# Sheet1.net
KiCad netlist of a schematic drawn in Altium Designer
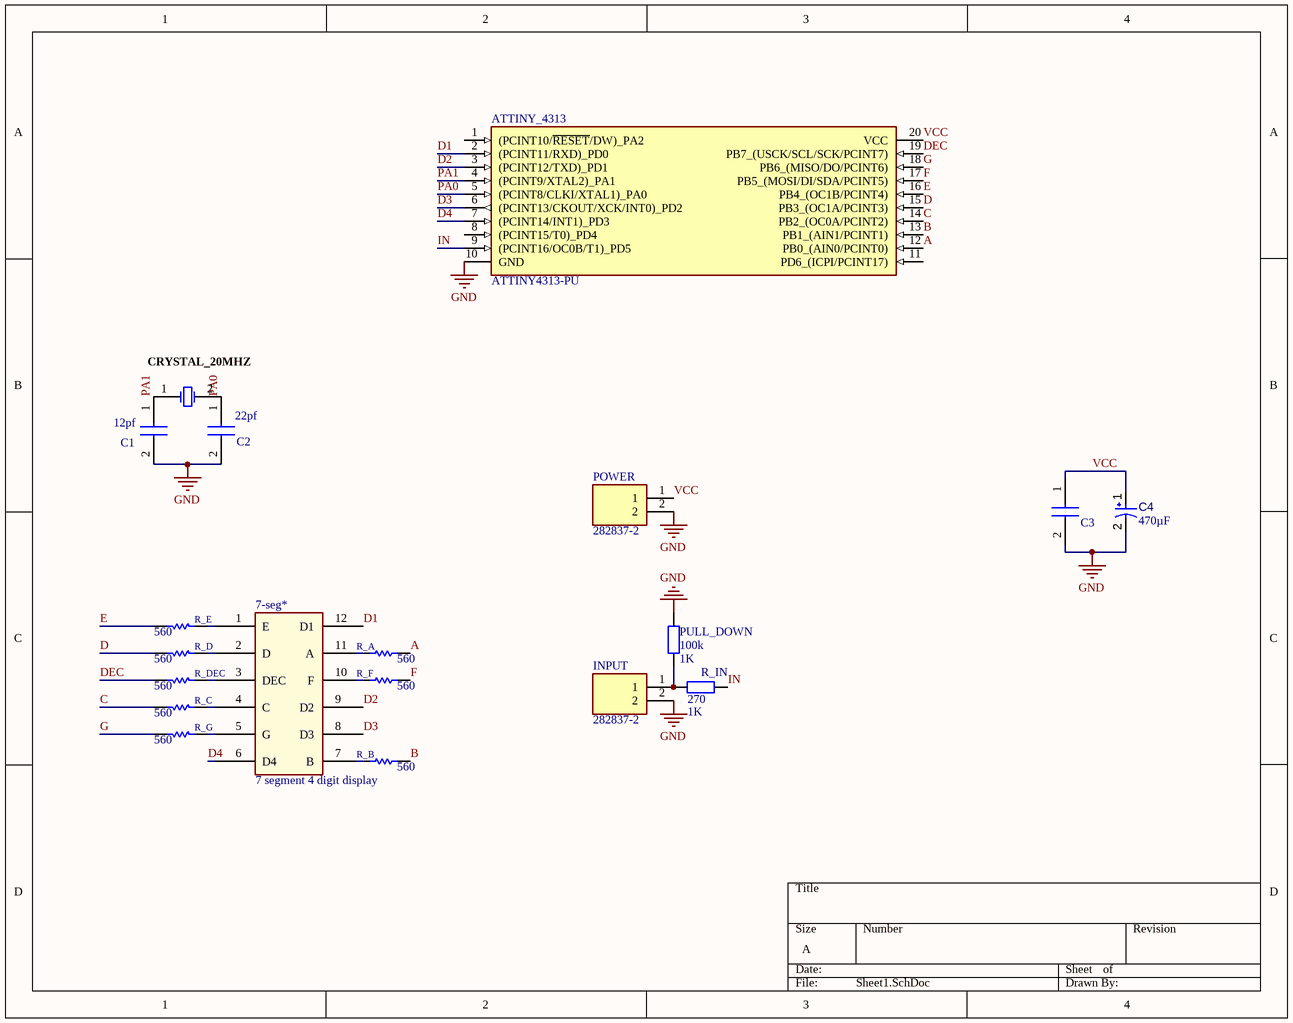
[diagram p0: Sheet1.SchDoc]

(export (version "E")
  (design (tool "Eeschema 10.0.6"))
  (components
    (comp (ref "7-seg*")
      (value "7 segment 4 digit display")
      (footprint "PCBComponent_1")
      (libsource (lib "7seg") (part "7 segment 4 digit display"))
    )
    (comp (ref "ATTINY_4313")
      (value "ATTINY4313-PU")
      (footprint "SamacSys:DIP794W56P254L2574H533Q20N")
      (description "Integrated Circuit")
      (fields (field (name "MOUSER PART NUMBER") "556-ATTINY4313-PU"))
      (libsource (lib "*") (part "ATTINY4313-PU"))
    )
    (comp (ref "C1")
      (value "12pf")
      (footprint "SamacSys:C320C104KCR5TA")
      (description "Capacitor")
      (fields
        (field (name "MANUFACTURER_PART_NUMBER") "C320C104KCR5TA")
        (field (name "MOUSER PART NUMBER") "80-C320C104KCR")
      )
      (libsource (lib "*") (part "C320C104KCR5TA"))
    )
    (comp (ref "C2")
      (value "22pf")
      (footprint "SamacSys:C320C104KCR5TA")
      (description "Capacitor")
      (fields
        (field (name "MANUFACTURER_PART_NUMBER") "C320C104KCR5TA")
        (field (name "MOUSER PART NUMBER") "80-C320C104KCR")
      )
      (libsource (lib "*") (part "C320C104KCR5TA"))
    )
    (comp (ref "C3")
      (value "C320C104KCR5TA")
      (footprint "SamacSys:C320C104KCR5TA")
      (description "Capacitor")
      (fields (field (name "MOUSER PART NUMBER") "80-C320C104KCR"))
      (libsource (lib "*") (part "C320C104KCR5TA"))
    )
    (comp (ref "C4")
      (value "470µF")
      (footprint "CAPPR65-350-1150X800X1250")
      (description "Aluminum Electrolytic Capacitor, 100 uF, +/- 20%, 50 V, -40 to 85 degC, 2-Pin THD, RoHS, Bulk")
      (fields (field (name "MANUFACTURER") "Panasonic") (field (name "TOLERANCE") "20%"))
      (libsource (lib "Ground Robotics") (part "CAP-P-2"))
    )
    (comp (ref "CRYSTAL_20MHZ")
      (value "FOXSLF/080-20")
      (footprint "FOX-FOXSLF080-20")
      (description "Resistance Weld Thru-Hole Crystal, 8 MHz, +/- 50 ppm, 10 pF, -20 to 70 degC, 2-Pin THD, RoHS, Bulk")
      (fields (field (name "MANUFACTURER") "FOX Electronics") (field (name "TOLERANCE") "50ppm"))
      (libsource (lib "Ground Robotics") (part "XTAL-1-2-2"))
    )
    (comp (ref "INPUT")
      (value "282837-2")
      (footprint "SamacSys:2828372")
      (description "Connector")
      (fields (field (name "MOUSER PART NUMBER") "571-2828372"))
      (libsource (lib "*") (part "282837-2"))
    )
    (comp (ref "POWER")
      (value "282837-2")
      (footprint "SamacSys:2828372")
      (description "Connector")
      (fields (field (name "MOUSER PART NUMBER") "571-2828372"))
      (libsource (lib "*") (part "282837-2"))
    )
    (comp (ref "PULL_DOWN")
      (value "100k")
      (footprint "AXIAL-0.4")
      (description "Resistor")
      (fields (field (name "ALTIUM_VALUE") "1K") (field (name "PUBLISHER") "Altium Limited"))
      (libsource (lib "Miscellaneous Devices") (part "Res2"))
    )
    (comp (ref "R_A")
      (value "560")
      (footprint "AXIAL-0.3")
      (description "Resistor")
      (fields (field (name "Comment") "Res1") (field (name "PUBLISHER") "Altium Limited"))
      (libsource (lib "Miscellaneous Devices") (part "Res1"))
    )
    (comp (ref "R_B")
      (value "560")
      (footprint "AXIAL-0.3")
      (description "Resistor")
      (fields (field (name "Comment") "Res1") (field (name "PUBLISHER") "Altium Limited"))
      (libsource (lib "Miscellaneous Devices") (part "Res1"))
    )
    (comp (ref "R_C")
      (value "560")
      (footprint "AXIAL-0.3")
      (description "Resistor")
      (fields (field (name "Comment") "Res1") (field (name "PUBLISHER") "Altium Limited"))
      (libsource (lib "Miscellaneous Devices") (part "Res1"))
    )
    (comp (ref "R_D")
      (value "560")
      (footprint "AXIAL-0.3")
      (description "Resistor")
      (fields (field (name "Comment") "Res1") (field (name "PUBLISHER") "Altium Limited"))
      (libsource (lib "Miscellaneous Devices") (part "Res1"))
    )
    (comp (ref "R_DEC")
      (value "560")
      (footprint "AXIAL-0.3")
      (description "Resistor")
      (fields (field (name "Comment") "Res1") (field (name "PUBLISHER") "Altium Limited"))
      (libsource (lib "Miscellaneous Devices") (part "Res1"))
    )
    (comp (ref "R_E")
      (value "560")
      (footprint "AXIAL-0.3")
      (description "Resistor")
      (fields (field (name "Comment") "Res1") (field (name "PUBLISHER") "Altium Limited"))
      (libsource (lib "Miscellaneous Devices") (part "Res1"))
    )
    (comp (ref "R_F")
      (value "560")
      (footprint "AXIAL-0.3")
      (description "Resistor")
      (fields (field (name "Comment") "Res1") (field (name "PUBLISHER") "Altium Limited"))
      (libsource (lib "Miscellaneous Devices") (part "Res1"))
    )
    (comp (ref "R_G")
      (value "560")
      (footprint "AXIAL-0.3")
      (description "Resistor")
      (fields (field (name "Comment") "Res1") (field (name "PUBLISHER") "Altium Limited"))
      (libsource (lib "Miscellaneous Devices") (part "Res1"))
    )
    (comp (ref "R_IN")
      (value "270")
      (footprint "AXIAL-0.4")
      (description "Resistor")
      (fields (field (name "ALTIUM_VALUE") "1K") (field (name "PUBLISHER") "Altium Limited"))
      (libsource (lib "") (part "Res2_1"))
    )
  )
  (nets
    (net (code "1") (name "/A") (class "Default")
      (node (ref "ATTINY_4313") (pin "12") (pinfunction "PB0_(AIN0/PCINT0)_12") (pintype "input"))
      (node (ref "R_A") (pin "2") (pinfunction "2_2") (pintype "passive"))
    )
    (net (code "2") (name "/B") (class "Default")
      (node (ref "ATTINY_4313") (pin "13") (pinfunction "PB1_(AIN1/PCINT1)_13") (pintype "input"))
      (node (ref "R_B") (pin "2") (pinfunction "2_2") (pintype "passive"))
    )
    (net (code "3") (name "/C") (class "Default")
      (node (ref "ATTINY_4313") (pin "14") (pinfunction "PB2_(OC0A/PCINT2)_14") (pintype "input"))
      (node (ref "R_C") (pin "2") (pinfunction "2_2") (pintype "passive"))
    )
    (net (code "4") (name "/D") (class "Default")
      (node (ref "ATTINY_4313") (pin "15") (pinfunction "PB3_(OC1A/PCINT3)_15") (pintype "input"))
      (node (ref "R_D") (pin "2") (pinfunction "2_2") (pintype "passive"))
    )
    (net (code "5") (name "/D1") (class "Default")
      (node (ref "7-seg*") (pin "12") (pinfunction "D1_12") (pintype "passive"))
      (node (ref "ATTINY_4313") (pin "2") (pinfunction "(PCINT11/RXD)_PD0_2") (pintype "input"))
    )
    (net (code "6") (name "/D2") (class "Default")
      (node (ref "7-seg*") (pin "9") (pinfunction "D2_9") (pintype "passive"))
      (node (ref "ATTINY_4313") (pin "3") (pinfunction "(PCINT12/TXD)_PD1_3") (pintype "input"))
    )
    (net (code "7") (name "/D3") (class "Default")
      (node (ref "7-seg*") (pin "8") (pinfunction "D3_8") (pintype "passive"))
      (node (ref "ATTINY_4313") (pin "6") (pinfunction "(PCINT13/CKOUT/XCK/INT0)_PD2_6") (pintype "output"))
    )
    (net (code "8") (name "/D4") (class "Default")
      (node (ref "7-seg*") (pin "6") (pinfunction "D4_6") (pintype "passive"))
      (node (ref "ATTINY_4313") (pin "7") (pinfunction "(PCINT14/INT1)_PD3_7") (pintype "input"))
    )
    (net (code "9") (name "/DEC") (class "Default")
      (node (ref "ATTINY_4313") (pin "19") (pinfunction "PB7_(USCK/SCL/SCK/PCINT7)_19") (pintype "input"))
      (node (ref "R_DEC") (pin "2") (pinfunction "2_2") (pintype "passive"))
    )
    (net (code "10") (name "/E") (class "Default")
      (node (ref "ATTINY_4313") (pin "16") (pinfunction "PB4_(OC1B/PCINT4)_16") (pintype "input"))
      (node (ref "R_E") (pin "2") (pinfunction "2_2") (pintype "passive"))
    )
    (net (code "11") (name "/F") (class "Default")
      (node (ref "ATTINY_4313") (pin "17") (pinfunction "PB5_(MOSI/DI/SDA/PCINT5)_17") (pintype "input"))
      (node (ref "R_F") (pin "2") (pinfunction "2_2") (pintype "passive"))
    )
    (net (code "12") (name "/G") (class "Default")
      (node (ref "ATTINY_4313") (pin "18") (pinfunction "PB6_(MISO/DO/PCINT6)_18") (pintype "input"))
      (node (ref "R_G") (pin "2") (pinfunction "2_2") (pintype "passive"))
    )
    (net (code "13") (name "/IN") (class "Default")
      (node (ref "ATTINY_4313") (pin "9") (pinfunction "(PCINT16/OC0B/T1)_PD5_9") (pintype "input"))
      (node (ref "R_IN") (pin "1") (pinfunction "1_1") (pintype "passive"))
    )
    (net (code "14") (name "/PA0") (class "Default")
      (node (ref "ATTINY_4313") (pin "5") (pinfunction "(PCINT8/CLKI/XTAL1)_PA0_5") (pintype "input"))
      (node (ref "C2") (pin "1") (pinfunction "1_1") (pintype "passive"))
      (node (ref "CRYSTAL_20MHZ") (pin "2") (pinfunction "2_2") (pintype "passive"))
    )
    (net (code "15") (name "/PA1") (class "Default")
      (node (ref "ATTINY_4313") (pin "4") (pinfunction "(PCINT9/XTAL2)_PA1_4") (pintype "input"))
      (node (ref "C1") (pin "1") (pinfunction "1_1") (pintype "passive"))
      (node (ref "CRYSTAL_20MHZ") (pin "1") (pinfunction "1_1") (pintype "passive"))
    )
    (net (code "16") (name "/VCC") (class "Default")
      (node (ref "ATTINY_4313") (pin "20") (pinfunction "VCC_20") (pintype "power_in"))
      (node (ref "C3") (pin "1") (pinfunction "1_1") (pintype "passive"))
      (node (ref "C4") (pin "1") (pinfunction "1_1") (pintype "passive"))
      (node (ref "POWER") (pin "1") (pinfunction "1_1") (pintype "passive"))
    )
    (net (code "17") (name "GND") (class "Default")
      (node (ref "ATTINY_4313") (pin "10") (pinfunction "GND_10") (pintype "power_in"))
      (node (ref "C1") (pin "2") (pinfunction "2_2") (pintype "passive"))
      (node (ref "C2") (pin "2") (pinfunction "2_2") (pintype "passive"))
      (node (ref "C3") (pin "2") (pinfunction "2_2") (pintype "passive"))
      (node (ref "C4") (pin "2") (pinfunction "2_2") (pintype "passive"))
      (node (ref "INPUT") (pin "2") (pinfunction "2_2") (pintype "passive"))
      (node (ref "POWER") (pin "2") (pinfunction "2_2") (pintype "passive"))
      (node (ref "PULL_DOWN") (pin "2") (pinfunction "2_2") (pintype "passive"))
    )
    (net (code "18") (name "Net-(7-seg*-A)") (class "Default")
      (node (ref "7-seg*") (pin "11") (pinfunction "A_11") (pintype "passive"))
      (node (ref "R_A") (pin "1") (pinfunction "1_1") (pintype "passive"))
    )
    (net (code "19") (name "Net-(7-seg*-B)") (class "Default")
      (node (ref "7-seg*") (pin "7") (pinfunction "B_7") (pintype "passive"))
      (node (ref "R_B") (pin "1") (pinfunction "1_1") (pintype "passive"))
    )
    (net (code "20") (name "Net-(7-seg*-C)") (class "Default")
      (node (ref "7-seg*") (pin "4") (pinfunction "C_4") (pintype "passive"))
      (node (ref "R_C") (pin "1") (pinfunction "1_1") (pintype "passive"))
    )
    (net (code "21") (name "Net-(7-seg*-D)") (class "Default")
      (node (ref "7-seg*") (pin "2") (pinfunction "D_2") (pintype "passive"))
      (node (ref "R_D") (pin "1") (pinfunction "1_1") (pintype "passive"))
    )
    (net (code "22") (name "Net-(7-seg*-DEC)") (class "Default")
      (node (ref "7-seg*") (pin "3") (pinfunction "DEC_3") (pintype "passive"))
      (node (ref "R_DEC") (pin "1") (pinfunction "1_1") (pintype "passive"))
    )
    (net (code "23") (name "Net-(7-seg*-E)") (class "Default")
      (node (ref "7-seg*") (pin "1") (pinfunction "E_1") (pintype "passive"))
      (node (ref "R_E") (pin "1") (pinfunction "1_1") (pintype "passive"))
    )
    (net (code "24") (name "Net-(7-seg*-F)") (class "Default")
      (node (ref "7-seg*") (pin "10") (pinfunction "F_10") (pintype "passive"))
      (node (ref "R_F") (pin "1") (pinfunction "1_1") (pintype "passive"))
    )
    (net (code "25") (name "Net-(7-seg*-G)") (class "Default")
      (node (ref "7-seg*") (pin "5") (pinfunction "G_5") (pintype "passive"))
      (node (ref "R_G") (pin "1") (pinfunction "1_1") (pintype "passive"))
    )
    (net (code "26") (name "Net-(INPUT-Pad1)") (class "Default")
      (node (ref "INPUT") (pin "1") (pinfunction "1_1") (pintype "passive"))
      (node (ref "PULL_DOWN") (pin "1") (pinfunction "1_1") (pintype "passive"))
      (node (ref "R_IN") (pin "2") (pinfunction "2_2") (pintype "passive"))
    )
    (net (code "27") (name "unconnected-(ATTINY_4313-(PCINT10{slash}~{RESET}{slash}DW)_PA2-Pad1)") (class "Default")
      (node (ref "ATTINY_4313") (pin "1") (pinfunction "(PCINT10/~{RESET}/DW)_PA2_1") (pintype "input"))
    )
    (net (code "28") (name "unconnected-(ATTINY_4313-(PCINT15{slash}T0)_PD4-Pad8)") (class "Default")
      (node (ref "ATTINY_4313") (pin "8") (pinfunction "(PCINT15/T0)_PD4_8") (pintype "input"))
    )
    (net (code "29") (name "unconnected-(ATTINY_4313-PD6_(ICPI{slash}PCINT17)-Pad11)") (class "Default")
      (node (ref "ATTINY_4313") (pin "11") (pinfunction "PD6_(ICPI/PCINT17)_11") (pintype "input"))
    )
  )
)
